# femtoUSB_r1_0_0_TQFP_BREADBOARD.net
KiCad netlist of a schematic drawn in EAGLE
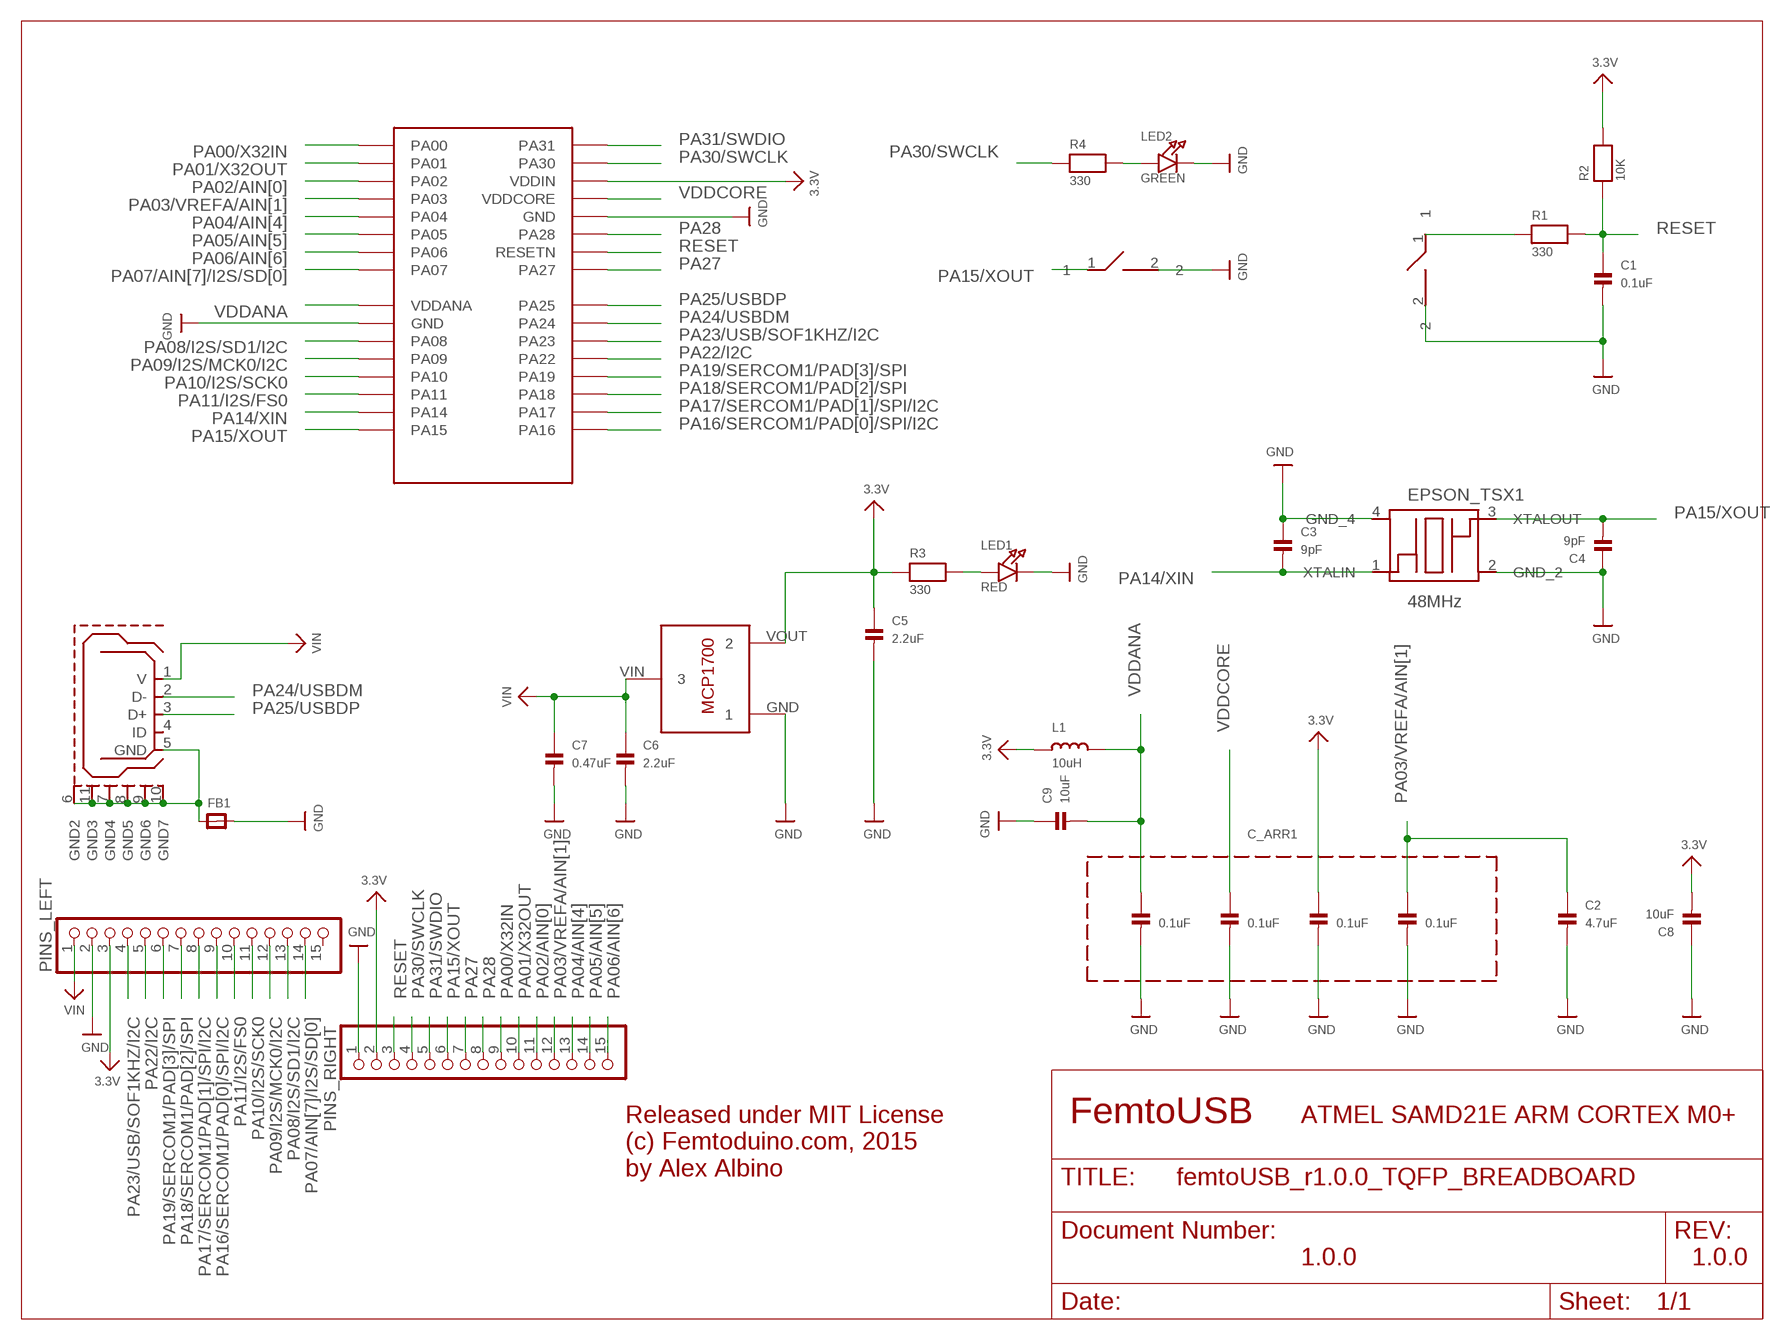
[diagram p0: schematic, sheet 1]

(export (version "E")
  (design (tool "Eeschema 10.0.6"))
  (components
    (comp (ref "BTN")
      (value "OMRON B3U-300P(M)")
      (footprint "eagle-import:SPST_SMD")
      (libsource (lib "eagle-import") (part "SPST_SMD"))
    )
    (comp (ref "C1")
      (value "0.1uF")
      (footprint "eagle-import:_0402MP")
      (fields (field (name "DIGIKEY_PART") "445-4958-1-ND"))
      (libsource (lib "eagle-import") (part "CAP_CERAMIC_0402MP"))
    )
    (comp (ref "C2")
      (value "4.7uF")
      (footprint "eagle-import:_0402MP")
      (libsource (lib "eagle-import") (part "CAP_CERAMIC_0402MP"))
    )
    (comp (ref "C3")
      (value "9pF")
      (footprint "eagle-import:_0402MP")
      (libsource (lib "eagle-import") (part "CAP_CERAMIC_0402MP"))
    )
    (comp (ref "C4")
      (value "9pF")
      (footprint "eagle-import:_0402MP")
      (libsource (lib "eagle-import") (part "CAP_CERAMIC_0402MP"))
    )
    (comp (ref "C5")
      (value "2.2uF")
      (footprint "eagle-import:_0402MP")
      (libsource (lib "eagle-import") (part "CAP_CERAMIC_0402MP"))
    )
    (comp (ref "C6")
      (value "2.2uF")
      (footprint "eagle-import:_0402MP")
      (libsource (lib "eagle-import") (part "CAP_CERAMIC_0402MP"))
    )
    (comp (ref "C7")
      (value "0.47uF")
      (footprint "eagle-import:_0402MP")
      (libsource (lib "eagle-import") (part "CAP_CERAMIC_0402MP"))
    )
    (comp (ref "C8")
      (value "10uF")
      (footprint "eagle-import:_0402MP")
      (libsource (lib "eagle-import") (part "CAP_CERAMIC_0402MP"))
    )
    (comp (ref "C9")
      (value "10uF")
      (footprint "eagle-import:_0402MP")
      (libsource (lib "eagle-import") (part "CAP_CERAMIC_0402MP"))
    )
    (comp (ref "C_ARR1")
      (value "0.1uF")
      (footprint "eagle-import:CAPACITOR_ARRAY_1206_MONO_1X4")
      (libsource (lib "eagle-import") (part "KEMET_CERAMIC_CAPACITOR_ARRAY_1X4"))
    )
    (comp (ref "EPSON_TSX1")
      (value "48MHz")
      (footprint "eagle-import:TSX-3225")
      (fields (field (name "DIGIKEY_PART") "TSX-3225 32.0000MF15X-B-ND"))
      (libsource (lib "eagle-import") (part "TSX-3225"))
    )
    (comp (ref "FB1")
      (value "FERRITE_0603MP")
      (footprint "eagle-import:_0603MP")
      (libsource (lib "eagle-import") (part "FERRITE_0603MP"))
    )
    (comp (ref "IC1")
      (value "ATSAMD21E18A-AU")
      (footprint "eagle-import:32-TQFP")
      (fields (field (name "DIGIKEY_PART") "ATSAMD21E18A-AU-ND"))
      (libsource (lib "eagle-import") (part "ATSAMD21E18A-AU"))
    )
    (comp (ref "L1")
      (value "10uH")
      (footprint "eagle-import:_0603MP")
      (libsource (lib "eagle-import") (part "INDUCTOR_0603MP"))
    )
    (comp (ref "LDO_VREG")
      (value "MCP1700T-3302E/TT")
      (footprint "eagle-import:MCP1700T-3302E_TT")
      (libsource (lib "eagle-import") (part "MCP1700T-3302E/TT"))
    )
    (comp (ref "LED1")
      (value "RED")
      (footprint "eagle-import:CHIPLED_0603_NOOUTLINE")
      (libsource (lib "eagle-import") (part "LED0603_NOOUTLINE"))
    )
    (comp (ref "LED2")
      (value "GREEN")
      (footprint "eagle-import:CHIPLED_0603_NOOUTLINE")
      (libsource (lib "eagle-import") (part "LED0603_NOOUTLINE"))
    )
    (comp (ref "MICRO_B_USB")
      (value "USB_MICROB")
      (footprint "eagle-import:USB_MICROB_PACKAGE")
      (libsource (lib "eagle-import") (part "USB_MICROB"))
    )
    (comp (ref "PINS_LEFT")
      (value "HEADER-1X15")
      (footprint "eagle-import:1X15_ROUND_70")
      (libsource (lib "eagle-import") (part "HEADER-1X15"))
    )
    (comp (ref "PINS_RIGHT")
      (value "HEADER-1X15")
      (footprint "eagle-import:1X15_ROUND_70")
      (libsource (lib "eagle-import") (part "HEADER-1X15"))
    )
    (comp (ref "R1")
      (value "330")
      (footprint "eagle-import:_0402MP")
      (fields (field (name "DIGIKEY_PART") "541-330JCT-ND"))
      (libsource (lib "eagle-import") (part "RESISTOR_0402MP"))
    )
    (comp (ref "R2")
      (value "10K")
      (footprint "eagle-import:_0402MP")
      (libsource (lib "eagle-import") (part "RESISTOR_0402MP"))
    )
    (comp (ref "R3")
      (value "330")
      (footprint "eagle-import:_0402MP")
      (libsource (lib "eagle-import") (part "RESISTOR_0402MP"))
    )
    (comp (ref "R4")
      (value "330")
      (footprint "eagle-import:_0402MP")
      (libsource (lib "eagle-import") (part "RESISTOR_0402MP"))
    )
    (comp (ref "U$38")
      (value "SPST_SMD")
      (footprint "eagle-import:SPST_SMD")
      (libsource (lib "eagle-import") (part "SPST_SMD"))
    )
  )
  (nets
    (net (code "1") (name "/PA00{slash}X32IN") (class "Default")
      (node (ref "IC1") (pin "1") (pinfunction "PA00_1") (pintype "bidirectional"))
      (node (ref "PINS_RIGHT") (pin "9") (pinfunction "9_9") (pintype "passive"))
    )
    (net (code "2") (name "/PA01{slash}X32OUT") (class "Default")
      (node (ref "IC1") (pin "2") (pinfunction "PA01_2") (pintype "bidirectional"))
      (node (ref "PINS_RIGHT") (pin "10") (pinfunction "10_10") (pintype "passive"))
    )
    (net (code "3") (name "/PA02{slash}AIN[0]") (class "Default")
      (node (ref "IC1") (pin "3") (pinfunction "PA02_3") (pintype "bidirectional"))
      (node (ref "PINS_RIGHT") (pin "11") (pinfunction "11_11") (pintype "passive"))
    )
    (net (code "4") (name "/PA03{slash}VREFA{slash}AIN[1]") (class "Default")
      (node (ref "C2") (pin "1") (pinfunction "P$1_1") (pintype "passive"))
      (node (ref "C_ARR1") (pin "7") (pinfunction "P$7_7") (pintype "passive"))
      (node (ref "IC1") (pin "4") (pinfunction "PA03_4") (pintype "bidirectional"))
      (node (ref "PINS_RIGHT") (pin "12") (pinfunction "12_12") (pintype "passive"))
    )
    (net (code "5") (name "/PA04{slash}AIN[4]") (class "Default")
      (node (ref "IC1") (pin "5") (pinfunction "PA04_5") (pintype "bidirectional"))
      (node (ref "PINS_RIGHT") (pin "13") (pinfunction "13_13") (pintype "passive"))
    )
    (net (code "6") (name "/PA05{slash}AIN[5]") (class "Default")
      (node (ref "IC1") (pin "6") (pinfunction "PA05_6") (pintype "bidirectional"))
      (node (ref "PINS_RIGHT") (pin "14") (pinfunction "14_14") (pintype "passive"))
    )
    (net (code "7") (name "/PA06{slash}AIN[6]") (class "Default")
      (node (ref "IC1") (pin "7") (pinfunction "PA06_7") (pintype "bidirectional"))
      (node (ref "PINS_RIGHT") (pin "15") (pinfunction "15_15") (pintype "passive"))
    )
    (net (code "8") (name "/PA07{slash}AIN[7]{slash}I2S{slash}SD[0]") (class "Default")
      (node (ref "IC1") (pin "8") (pinfunction "PA07_8") (pintype "bidirectional"))
      (node (ref "PINS_LEFT") (pin "14") (pinfunction "14_14") (pintype "passive"))
    )
    (net (code "9") (name "/PA08{slash}I2S{slash}SD1{slash}I2C") (class "Default")
      (node (ref "IC1") (pin "11") (pinfunction "PA08_11") (pintype "bidirectional"))
      (node (ref "PINS_LEFT") (pin "13") (pinfunction "13_13") (pintype "passive"))
    )
    (net (code "10") (name "/PA09{slash}I2S{slash}MCK0{slash}I2C") (class "Default")
      (node (ref "IC1") (pin "12") (pinfunction "PA09_12") (pintype "bidirectional"))
      (node (ref "PINS_LEFT") (pin "12") (pinfunction "12_12") (pintype "passive"))
    )
    (net (code "11") (name "/PA10{slash}I2S{slash}SCK0") (class "Default")
      (node (ref "IC1") (pin "13") (pinfunction "PA10_13") (pintype "bidirectional"))
      (node (ref "PINS_LEFT") (pin "11") (pinfunction "11_11") (pintype "passive"))
    )
    (net (code "12") (name "/PA11{slash}I2S{slash}FS0") (class "Default")
      (node (ref "IC1") (pin "14") (pinfunction "PA11_14") (pintype "bidirectional"))
      (node (ref "PINS_LEFT") (pin "10") (pinfunction "10_10") (pintype "passive"))
    )
    (net (code "13") (name "/PA14{slash}XIN") (class "Default")
      (node (ref "C3") (pin "2") (pinfunction "P$2_2") (pintype "passive"))
      (node (ref "EPSON_TSX1") (pin "1") (pinfunction "XTALIN_1") (pintype "bidirectional"))
      (node (ref "IC1") (pin "15") (pinfunction "PA14_15") (pintype "bidirectional"))
    )
    (net (code "14") (name "/PA15{slash}XOUT") (class "Default")
      (node (ref "C4") (pin "2") (pinfunction "P$2_2") (pintype "passive"))
      (node (ref "EPSON_TSX1") (pin "3") (pinfunction "XTALOUT_3") (pintype "bidirectional"))
      (node (ref "IC1") (pin "16") (pinfunction "PA15_16") (pintype "bidirectional"))
      (node (ref "PINS_RIGHT") (pin "6") (pinfunction "6_6") (pintype "passive"))
      (node (ref "U$38") (pin "1") (pinfunction "1_1") (pintype "bidirectional"))
    )
    (net (code "15") (name "/PA16{slash}SERCOM1{slash}PAD[0]{slash}SPI{slash}I2C") (class "Default")
      (node (ref "IC1") (pin "17") (pinfunction "PA16_17") (pintype "bidirectional"))
      (node (ref "PINS_LEFT") (pin "9") (pinfunction "9_9") (pintype "passive"))
    )
    (net (code "16") (name "/PA17{slash}SERCOM1{slash}PAD[1]{slash}SPI{slash}I2C") (class "Default")
      (node (ref "IC1") (pin "18") (pinfunction "PA17_18") (pintype "bidirectional"))
      (node (ref "PINS_LEFT") (pin "8") (pinfunction "8_8") (pintype "passive"))
    )
    (net (code "17") (name "/PA18{slash}SERCOM1{slash}PAD[2]{slash}SPI") (class "Default")
      (node (ref "IC1") (pin "19") (pinfunction "PA18_19") (pintype "bidirectional"))
      (node (ref "PINS_LEFT") (pin "7") (pinfunction "7_7") (pintype "passive"))
    )
    (net (code "18") (name "/PA19{slash}SERCOM1{slash}PAD[3]{slash}SPI") (class "Default")
      (node (ref "IC1") (pin "20") (pinfunction "PA19_20") (pintype "bidirectional"))
      (node (ref "PINS_LEFT") (pin "6") (pinfunction "6_6") (pintype "passive"))
    )
    (net (code "19") (name "/PA22{slash}I2C") (class "Default")
      (node (ref "IC1") (pin "21") (pinfunction "PA22_21") (pintype "bidirectional"))
      (node (ref "PINS_LEFT") (pin "5") (pinfunction "5_5") (pintype "passive"))
    )
    (net (code "20") (name "/PA23{slash}USB{slash}SOF1KHZ{slash}I2C") (class "Default")
      (node (ref "IC1") (pin "22") (pinfunction "PA23_22") (pintype "bidirectional"))
      (node (ref "PINS_LEFT") (pin "4") (pinfunction "4_4") (pintype "passive"))
    )
    (net (code "21") (name "/PA24{slash}USBDM") (class "Default")
      (node (ref "IC1") (pin "23") (pinfunction "PA24_23") (pintype "bidirectional"))
      (node (ref "MICRO_B_USB") (pin "2") (pinfunction "D-_2") (pintype "bidirectional"))
    )
    (net (code "22") (name "/PA25{slash}USBDP") (class "Default")
      (node (ref "IC1") (pin "24") (pinfunction "PA25_24") (pintype "bidirectional"))
      (node (ref "MICRO_B_USB") (pin "3") (pinfunction "D+_3") (pintype "bidirectional"))
    )
    (net (code "23") (name "/PA27") (class "Default")
      (node (ref "IC1") (pin "25") (pinfunction "PA27_25") (pintype "bidirectional"))
      (node (ref "PINS_RIGHT") (pin "7") (pinfunction "7_7") (pintype "passive"))
    )
    (net (code "24") (name "/PA28") (class "Default")
      (node (ref "IC1") (pin "27") (pinfunction "PA28_27") (pintype "bidirectional"))
      (node (ref "PINS_RIGHT") (pin "8") (pinfunction "8_8") (pintype "passive"))
    )
    (net (code "25") (name "/PA30{slash}SWCLK") (class "Default")
      (node (ref "IC1") (pin "31") (pinfunction "PA30_31") (pintype "bidirectional"))
      (node (ref "PINS_RIGHT") (pin "4") (pinfunction "4_4") (pintype "passive"))
      (node (ref "R4") (pin "1") (pinfunction "1_1") (pintype "passive"))
    )
    (net (code "26") (name "/PA31{slash}SWDIO") (class "Default")
      (node (ref "IC1") (pin "32") (pinfunction "PA31_32") (pintype "bidirectional"))
      (node (ref "PINS_RIGHT") (pin "5") (pinfunction "5_5") (pintype "passive"))
    )
    (net (code "27") (name "/RESET") (class "Default")
      (node (ref "C1") (pin "1") (pinfunction "P$1_1") (pintype "passive"))
      (node (ref "IC1") (pin "26") (pinfunction "RESETN_26") (pintype "bidirectional"))
      (node (ref "PINS_RIGHT") (pin "3") (pinfunction "3_3") (pintype "passive"))
      (node (ref "R1") (pin "2") (pinfunction "2_2") (pintype "passive"))
      (node (ref "R2") (pin "1") (pinfunction "1_1") (pintype "passive"))
    )
    (net (code "28") (name "/VDDANA") (class "Default")
      (node (ref "C9") (pin "2") (pinfunction "P$2_2") (pintype "passive"))
      (node (ref "C_ARR1") (pin "1") (pinfunction "P$1_1") (pintype "passive"))
      (node (ref "IC1") (pin "9") (pinfunction "VDDANA_9") (pintype "bidirectional"))
      (node (ref "L1") (pin "2") (pinfunction "2_2") (pintype "passive"))
    )
    (net (code "29") (name "/VDDCORE") (class "Default")
      (node (ref "C_ARR1") (pin "3") (pinfunction "P$3_3") (pintype "passive"))
      (node (ref "IC1") (pin "29") (pinfunction "VDDCORE_29") (pintype "bidirectional"))
    )
    (net (code "30") (name "3.3V") (class "Default")
      (node (ref "C5") (pin "1") (pinfunction "P$1_1") (pintype "passive"))
      (node (ref "C8") (pin "2") (pinfunction "P$2_2") (pintype "passive"))
      (node (ref "C_ARR1") (pin "5") (pinfunction "P$5_5") (pintype "passive"))
      (node (ref "IC1") (pin "30") (pinfunction "VDDIN_30") (pintype "bidirectional"))
      (node (ref "L1") (pin "1") (pinfunction "1_1") (pintype "passive"))
      (node (ref "LDO_VREG") (pin "VOUT") (pinfunction "2_VOUT") (pintype "bidirectional"))
      (node (ref "PINS_LEFT") (pin "3") (pinfunction "3_3") (pintype "passive"))
      (node (ref "PINS_RIGHT") (pin "2") (pinfunction "2_2") (pintype "passive"))
      (node (ref "R2") (pin "2") (pinfunction "2_2") (pintype "passive"))
      (node (ref "R3") (pin "1") (pinfunction "1_1") (pintype "passive"))
    )
    (net (code "31") (name "GND") (class "Default")
      (node (ref "BTN") (pin "2") (pinfunction "2_2") (pintype "bidirectional"))
      (node (ref "C1") (pin "2") (pinfunction "P$2_2") (pintype "passive"))
      (node (ref "C2") (pin "2") (pinfunction "P$2_2") (pintype "passive"))
      (node (ref "C3") (pin "1") (pinfunction "P$1_1") (pintype "passive"))
      (node (ref "C4") (pin "1") (pinfunction "P$1_1") (pintype "passive"))
      (node (ref "C5") (pin "2") (pinfunction "P$2_2") (pintype "passive"))
      (node (ref "C6") (pin "2") (pinfunction "P$2_2") (pintype "passive"))
      (node (ref "C7") (pin "2") (pinfunction "P$2_2") (pintype "passive"))
      (node (ref "C8") (pin "1") (pinfunction "P$1_1") (pintype "passive"))
      (node (ref "C9") (pin "1") (pinfunction "P$1_1") (pintype "passive"))
      (node (ref "C_ARR1") (pin "2") (pinfunction "P$2_2") (pintype "passive"))
      (node (ref "C_ARR1") (pin "4") (pinfunction "P$4_4") (pintype "passive"))
      (node (ref "C_ARR1") (pin "6") (pinfunction "P$6_6") (pintype "passive"))
      (node (ref "C_ARR1") (pin "8") (pinfunction "P$8_8") (pintype "passive"))
      (node (ref "EPSON_TSX1") (pin "2") (pinfunction "GND_2_2") (pintype "bidirectional"))
      (node (ref "EPSON_TSX1") (pin "4") (pinfunction "GND_4_4") (pintype "bidirectional"))
      (node (ref "FB1") (pin "2") (pinfunction "P$2_2") (pintype "passive"))
      (node (ref "IC1") (pin "10") (pinfunction "GND_10") (pintype "bidirectional"))
      (node (ref "IC1") (pin "28") (pinfunction "GND_28") (pintype "bidirectional"))
      (node (ref "LDO_VREG") (pin "GND") (pinfunction "1_GND") (pintype "bidirectional"))
      (node (ref "LED1") (pin "C") (pinfunction "C_C") (pintype "passive"))
      (node (ref "LED2") (pin "C") (pinfunction "C_C") (pintype "passive"))
      (node (ref "PINS_LEFT") (pin "2") (pinfunction "2_2") (pintype "passive"))
      (node (ref "PINS_RIGHT") (pin "1") (pinfunction "1_1") (pintype "passive"))
      (node (ref "U$38") (pin "2") (pinfunction "2_2") (pintype "bidirectional"))
    )
    (net (code "32") (name "Net-(BTN-Pad1)") (class "Default")
      (node (ref "BTN") (pin "1") (pinfunction "1_1") (pintype "bidirectional"))
      (node (ref "R1") (pin "1") (pinfunction "1_1") (pintype "passive"))
    )
    (net (code "33") (name "Net-(FB1-P$1)") (class "Default")
      (node (ref "FB1") (pin "1") (pinfunction "P$1_1") (pintype "passive"))
      (node (ref "MICRO_B_USB") (pin "10") (pinfunction "GND7_10") (pintype "bidirectional"))
      (node (ref "MICRO_B_USB") (pin "11") (pinfunction "GND3_11") (pintype "bidirectional"))
      (node (ref "MICRO_B_USB") (pin "5") (pinfunction "GND_5") (pintype "bidirectional"))
      (node (ref "MICRO_B_USB") (pin "6") (pinfunction "GND2_6") (pintype "bidirectional"))
      (node (ref "MICRO_B_USB") (pin "7") (pinfunction "GND4_7") (pintype "bidirectional"))
      (node (ref "MICRO_B_USB") (pin "8") (pinfunction "GND5_8") (pintype "bidirectional"))
      (node (ref "MICRO_B_USB") (pin "9") (pinfunction "GND6_9") (pintype "bidirectional"))
    )
    (net (code "34") (name "Net-(LED1-PadA)") (class "Default")
      (node (ref "LED1") (pin "A") (pinfunction "A_A") (pintype "passive"))
      (node (ref "R3") (pin "2") (pinfunction "2_2") (pintype "passive"))
    )
    (net (code "35") (name "Net-(LED2-PadA)") (class "Default")
      (node (ref "LED2") (pin "A") (pinfunction "A_A") (pintype "passive"))
      (node (ref "R4") (pin "2") (pinfunction "2_2") (pintype "passive"))
    )
    (net (code "36") (name "VIN") (class "Default")
      (node (ref "C6") (pin "1") (pinfunction "P$1_1") (pintype "passive"))
      (node (ref "C7") (pin "1") (pinfunction "P$1_1") (pintype "passive"))
      (node (ref "LDO_VREG") (pin "VIN") (pinfunction "3_VIN") (pintype "bidirectional"))
      (node (ref "MICRO_B_USB") (pin "1") (pinfunction "V_1") (pintype "bidirectional"))
      (node (ref "PINS_LEFT") (pin "1") (pinfunction "1_1") (pintype "passive"))
    )
    (net (code "37") (name "unconnected-(MICRO_B_USB-ID-Pad4)") (class "Default")
      (node (ref "MICRO_B_USB") (pin "4") (pinfunction "ID_4") (pintype "bidirectional"))
    )
    (net (code "38") (name "unconnected-(PINS_LEFT-Pad15)") (class "Default")
      (node (ref "PINS_LEFT") (pin "15") (pinfunction "15_15") (pintype "passive"))
    )
  )
)
